# RandomNumberGenerator.net
KiCad netlist of a schematic drawn in Altium Designer
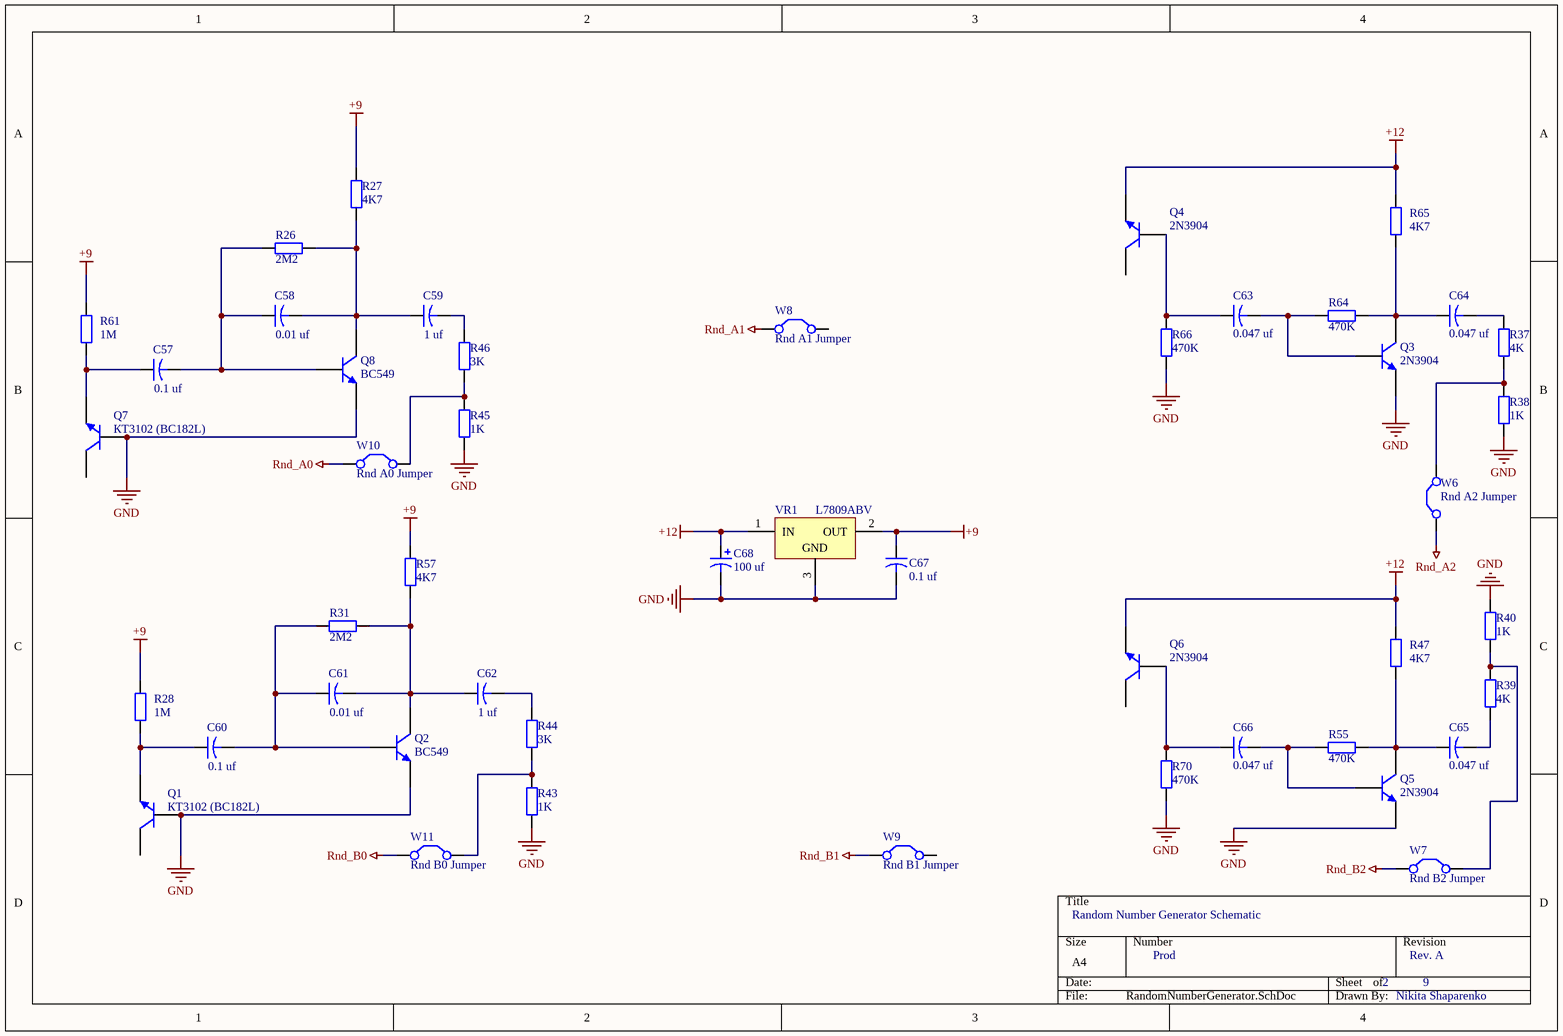
[diagram p0: RandomNumberGenerator.SchDoc]

(export (version "E")
  (design (tool "Eeschema 10.0.6"))
  (components
    (comp (ref "C57")
      (value "0.1 uf")
      (footprint "CAPR5-4X5")
      (description "Capacitor")
      (fields (field (name "Comment") "Cap2") (field (name "PUBLISHER") "Altium Limited"))
      (libsource (lib "Miscellaneous Devices") (part "Cap2"))
    )
    (comp (ref "C58")
      (value "0.01 uf")
      (footprint "CAPR5-4X5")
      (description "Capacitor")
      (fields (field (name "Comment") "Cap2") (field (name "PUBLISHER") "Altium Limited"))
      (libsource (lib "Miscellaneous Devices") (part "Cap2"))
    )
    (comp (ref "C59")
      (value "1 uf")
      (footprint "CAPR5-4X5")
      (description "Capacitor")
      (fields (field (name "Comment") "Cap2") (field (name "PUBLISHER") "Altium Limited"))
      (libsource (lib "Miscellaneous Devices") (part "Cap2"))
    )
    (comp (ref "C60")
      (value "0.1 uf")
      (footprint "CAPR5-4X5")
      (description "Capacitor")
      (fields (field (name "Comment") "Cap2") (field (name "PUBLISHER") "Altium Limited"))
      (libsource (lib "Miscellaneous Devices") (part "Cap2"))
    )
    (comp (ref "C61")
      (value "0.01 uf")
      (footprint "CAPR5-4X5")
      (description "Capacitor")
      (fields (field (name "Comment") "Cap2") (field (name "PUBLISHER") "Altium Limited"))
      (libsource (lib "Miscellaneous Devices") (part "Cap2"))
    )
    (comp (ref "C62")
      (value "1 uf")
      (footprint "CAPR5-4X5")
      (description "Capacitor")
      (fields (field (name "Comment") "Cap2") (field (name "PUBLISHER") "Altium Limited"))
      (libsource (lib "Miscellaneous Devices") (part "Cap2"))
    )
    (comp (ref "C63")
      (value "0.047 uf")
      (footprint "CAPR5-4X5")
      (description "Capacitor")
      (fields (field (name "Comment") "Cap2") (field (name "PUBLISHER") "Altium Limited"))
      (libsource (lib "Miscellaneous Devices") (part "Cap2"))
    )
    (comp (ref "C64")
      (value "0.047 uf")
      (footprint "CAPR5-4X5")
      (description "Capacitor")
      (fields (field (name "Comment") "Cap2") (field (name "PUBLISHER") "Altium Limited"))
      (libsource (lib "Miscellaneous Devices") (part "Cap2"))
    )
    (comp (ref "C65")
      (value "0.047 uf")
      (footprint "CAPR5-4X5")
      (description "Capacitor")
      (fields (field (name "Comment") "Cap2") (field (name "PUBLISHER") "Altium Limited"))
      (libsource (lib "Miscellaneous Devices") (part "Cap2"))
    )
    (comp (ref "C66")
      (value "0.047 uf")
      (footprint "CAPR5-4X5")
      (description "Capacitor")
      (fields (field (name "Comment") "Cap2") (field (name "PUBLISHER") "Altium Limited"))
      (libsource (lib "Miscellaneous Devices") (part "Cap2"))
    )
    (comp (ref "C67")
      (value "0.1 uf")
      (footprint "CAPR5-4X5")
      (description "Capacitor")
      (fields (field (name "Comment") "Cap2") (field (name "PUBLISHER") "Altium Limited"))
      (libsource (lib "Miscellaneous Devices") (part "Cap2"))
    )
    (comp (ref "C68")
      (value "100 uf")
      (footprint "RAD-0.2")
      (description "Polarized Capacitor (Radial)")
      (fields (field (name "Comment") "Cap Pol1") (field (name "PUBLISHER") "Altium Limited"))
      (libsource (lib "Miscellaneous Devices") (part "Cap Pol1"))
    )
    (comp (ref "Q1")
      (value "КТ3102 (BC182L)")
      (footprint "TO-226-AA")
      (description "NPN Bipolar Transistor")
      (fields (field (name "PUBLISHER") "Altium Limited"))
      (libsource (lib "Miscellaneous Devices") (part "NPN"))
    )
    (comp (ref "Q2")
      (value "BC549")
      (footprint "TO-226-AA")
      (description "NPN Bipolar Transistor")
      (fields (field (name "PUBLISHER") "Altium Limited"))
      (libsource (lib "Miscellaneous Devices") (part "NPN"))
    )
    (comp (ref "Q3")
      (value "2N3904")
      (footprint "TO-226-AA")
      (description "NPN Bipolar Transistor")
      (fields (field (name "PUBLISHER") "Altium Limited"))
      (libsource (lib "Miscellaneous Devices") (part "NPN"))
    )
    (comp (ref "Q4")
      (value "2N3904")
      (footprint "TO-226-AA")
      (description "NPN Bipolar Transistor")
      (fields (field (name "PUBLISHER") "Altium Limited"))
      (libsource (lib "Miscellaneous Devices") (part "NPN"))
    )
    (comp (ref "Q5")
      (value "2N3904")
      (footprint "TO-226-AA")
      (description "NPN Bipolar Transistor")
      (fields (field (name "PUBLISHER") "Altium Limited"))
      (libsource (lib "Miscellaneous Devices") (part "NPN"))
    )
    (comp (ref "Q6")
      (value "2N3904")
      (footprint "TO-226-AA")
      (description "NPN Bipolar Transistor")
      (fields (field (name "PUBLISHER") "Altium Limited"))
      (libsource (lib "Miscellaneous Devices") (part "NPN"))
    )
    (comp (ref "Q7")
      (value "КТ3102 (BC182L)")
      (footprint "TO-226-AA")
      (description "NPN Bipolar Transistor")
      (fields (field (name "PUBLISHER") "Altium Limited"))
      (libsource (lib "Miscellaneous Devices") (part "NPN"))
    )
    (comp (ref "Q8")
      (value "BC549")
      (footprint "TO-226-AA")
      (description "NPN Bipolar Transistor")
      (fields (field (name "PUBLISHER") "Altium Limited"))
      (libsource (lib "Miscellaneous Devices") (part "NPN"))
    )
    (comp (ref "R26")
      (value "2M2")
      (footprint "AXIAL-0.4")
      (description "Resistor")
      (fields (field (name "Comment") "Res2") (field (name "PUBLISHER") "Altium Limited"))
      (libsource (lib "") (part "Res2_1"))
    )
    (comp (ref "R27")
      (value "4K7")
      (footprint "AXIAL-0.4")
      (description "Resistor")
      (fields (field (name "Comment") "Res2") (field (name "PUBLISHER") "Altium Limited"))
      (libsource (lib "Miscellaneous Devices") (part "Res2"))
    )
    (comp (ref "R28")
      (value "1M")
      (footprint "AXIAL-0.4")
      (description "Resistor")
      (fields (field (name "Comment") "Res2") (field (name "PUBLISHER") "Altium Limited"))
      (libsource (lib "Miscellaneous Devices") (part "Res2"))
    )
    (comp (ref "R31")
      (value "2M2")
      (footprint "AXIAL-0.4")
      (description "Resistor")
      (fields (field (name "Comment") "Res2") (field (name "PUBLISHER") "Altium Limited"))
      (libsource (lib "") (part "Res2_1"))
    )
    (comp (ref "R37")
      (value "4K")
      (footprint "AXIAL-0.4")
      (description "Resistor")
      (fields (field (name "Comment") "Res2") (field (name "PUBLISHER") "Altium Limited"))
      (libsource (lib "Miscellaneous Devices") (part "Res2"))
    )
    (comp (ref "R38")
      (value "1K")
      (footprint "AXIAL-0.4")
      (description "Resistor")
      (fields (field (name "Comment") "Res2") (field (name "PUBLISHER") "Altium Limited"))
      (libsource (lib "Miscellaneous Devices") (part "Res2"))
    )
    (comp (ref "R39")
      (value "4K")
      (footprint "AXIAL-0.4")
      (description "Resistor")
      (fields (field (name "Comment") "Res2") (field (name "PUBLISHER") "Altium Limited"))
      (libsource (lib "") (part "Res2_2"))
    )
    (comp (ref "R40")
      (value "1K")
      (footprint "AXIAL-0.4")
      (description "Resistor")
      (fields (field (name "Comment") "Res2") (field (name "PUBLISHER") "Altium Limited"))
      (libsource (lib "") (part "Res2_2"))
    )
    (comp (ref "R43")
      (value "1K")
      (footprint "AXIAL-0.4")
      (description "Resistor")
      (fields (field (name "Comment") "Res2") (field (name "PUBLISHER") "Altium Limited"))
      (libsource (lib "Miscellaneous Devices") (part "Res2"))
    )
    (comp (ref "R44")
      (value "3K")
      (footprint "AXIAL-0.4")
      (description "Resistor")
      (fields (field (name "Comment") "Res2") (field (name "PUBLISHER") "Altium Limited"))
      (libsource (lib "Miscellaneous Devices") (part "Res2"))
    )
    (comp (ref "R45")
      (value "1K")
      (footprint "AXIAL-0.4")
      (description "Resistor")
      (fields (field (name "Comment") "Res2") (field (name "PUBLISHER") "Altium Limited"))
      (libsource (lib "Miscellaneous Devices") (part "Res2"))
    )
    (comp (ref "R46")
      (value "3K")
      (footprint "AXIAL-0.4")
      (description "Resistor")
      (fields (field (name "Comment") "Res2") (field (name "PUBLISHER") "Altium Limited"))
      (libsource (lib "Miscellaneous Devices") (part "Res2"))
    )
    (comp (ref "R47")
      (value "4K7")
      (footprint "AXIAL-0.4")
      (description "Resistor")
      (fields (field (name "Comment") "Res2") (field (name "PUBLISHER") "Altium Limited"))
      (libsource (lib "Miscellaneous Devices") (part "Res2"))
    )
    (comp (ref "R55")
      (value "470K")
      (footprint "AXIAL-0.4")
      (description "Resistor")
      (fields (field (name "Comment") "Res2") (field (name "PUBLISHER") "Altium Limited"))
      (libsource (lib "") (part "Res2_1"))
    )
    (comp (ref "R57")
      (value "4K7")
      (footprint "AXIAL-0.4")
      (description "Resistor")
      (fields (field (name "Comment") "Res2") (field (name "PUBLISHER") "Altium Limited"))
      (libsource (lib "Miscellaneous Devices") (part "Res2"))
    )
    (comp (ref "R61")
      (value "1M")
      (footprint "AXIAL-0.4")
      (description "Resistor")
      (fields (field (name "Comment") "Res2") (field (name "PUBLISHER") "Altium Limited"))
      (libsource (lib "Miscellaneous Devices") (part "Res2"))
    )
    (comp (ref "R64")
      (value "470K")
      (footprint "AXIAL-0.4")
      (description "Resistor")
      (fields (field (name "Comment") "Res2") (field (name "PUBLISHER") "Altium Limited"))
      (libsource (lib "") (part "Res2_1"))
    )
    (comp (ref "R65")
      (value "4K7")
      (footprint "AXIAL-0.4")
      (description "Resistor")
      (fields (field (name "Comment") "Res2") (field (name "PUBLISHER") "Altium Limited"))
      (libsource (lib "Miscellaneous Devices") (part "Res2"))
    )
    (comp (ref "R66")
      (value "470K")
      (footprint "AXIAL-0.4")
      (description "Resistor")
      (fields (field (name "Comment") "Res2") (field (name "PUBLISHER") "Altium Limited"))
      (libsource (lib "Miscellaneous Devices") (part "Res2"))
    )
    (comp (ref "R70")
      (value "470K")
      (footprint "AXIAL-0.4")
      (description "Resistor")
      (fields (field (name "Comment") "Res2") (field (name "PUBLISHER") "Altium Limited"))
      (libsource (lib "Miscellaneous Devices") (part "Res2"))
    )
    (comp (ref "VR1")
      (value "L7809ABV")
      (footprint "TO220ABN")
      (description "Precision 1A Regulator")
      (fields (field (name "PUBLISHER") "Altium Limited"))
      (libsource (lib "ST Power Mgt Voltage Regulator") (part "L7809ABV"))
    )
    (comp (ref "W6")
      (value "Rnd A2 Jumper")
      (footprint "RAD-0.2")
      (description "Jumper Wire")
      (fields (field (name "PUBLISHER") "Altium Limited"))
      (libsource (lib "Miscellaneous Devices") (part "Jumper"))
    )
    (comp (ref "W7")
      (value "Rnd B2 Jumper")
      (footprint "RAD-0.2")
      (description "Jumper Wire")
      (fields (field (name "PUBLISHER") "Altium Limited"))
      (libsource (lib "Miscellaneous Devices") (part "Jumper"))
    )
    (comp (ref "W8")
      (value "Rnd A1 Jumper")
      (footprint "RAD-0.2")
      (description "Jumper Wire")
      (fields (field (name "PUBLISHER") "Altium Limited"))
      (libsource (lib "Miscellaneous Devices") (part "Jumper"))
    )
    (comp (ref "W9")
      (value "Rnd B1 Jumper")
      (footprint "RAD-0.2")
      (description "Jumper Wire")
      (fields (field (name "PUBLISHER") "Altium Limited"))
      (libsource (lib "Miscellaneous Devices") (part "Jumper"))
    )
    (comp (ref "W10")
      (value "Rnd A0 Jumper")
      (footprint "RAD-0.2")
      (description "Jumper Wire")
      (fields (field (name "PUBLISHER") "Altium Limited"))
      (libsource (lib "Miscellaneous Devices") (part "Jumper"))
    )
    (comp (ref "W11")
      (value "Rnd B0 Jumper")
      (footprint "RAD-0.2")
      (description "Jumper Wire")
      (fields (field (name "PUBLISHER") "Altium Limited"))
      (libsource (lib "Miscellaneous Devices") (part "Jumper"))
    )
  )
  (nets
    (net (code "1") (name "+9") (class "Default")
      (node (ref "C67") (pin "1") (pinfunction "1_1") (pintype "passive"))
      (node (ref "R27") (pin "2") (pinfunction "2_2") (pintype "passive"))
      (node (ref "R28") (pin "2") (pinfunction "2_2") (pintype "passive"))
      (node (ref "R57") (pin "2") (pinfunction "2_2") (pintype "passive"))
      (node (ref "R61") (pin "2") (pinfunction "2_2") (pintype "passive"))
      (node (ref "VR1") (pin "2") (pinfunction "OUT_2") (pintype "power_in"))
    )
    (net (code "2") (name "+12") (class "Default")
      (node (ref "C68") (pin "1") (pinfunction "1_1") (pintype "passive"))
      (node (ref "Q4") (pin "3") (pinfunction "E_3") (pintype "passive"))
      (node (ref "Q6") (pin "3") (pinfunction "E_3") (pintype "passive"))
      (node (ref "R47") (pin "2") (pinfunction "2_2") (pintype "passive"))
      (node (ref "R65") (pin "2") (pinfunction "2_2") (pintype "passive"))
      (node (ref "VR1") (pin "1") (pinfunction "IN_1") (pintype "power_in"))
    )
    (net (code "3") (name "GND") (class "Default")
      (node (ref "C67") (pin "2") (pinfunction "2_2") (pintype "passive"))
      (node (ref "C68") (pin "2") (pinfunction "2_2") (pintype "passive"))
      (node (ref "Q1") (pin "2") (pinfunction "B_2") (pintype "passive"))
      (node (ref "Q2") (pin "3") (pinfunction "E_3") (pintype "passive"))
      (node (ref "Q3") (pin "3") (pinfunction "E_3") (pintype "passive"))
      (node (ref "Q5") (pin "3") (pinfunction "E_3") (pintype "passive"))
      (node (ref "Q7") (pin "2") (pinfunction "B_2") (pintype "passive"))
      (node (ref "Q8") (pin "3") (pinfunction "E_3") (pintype "passive"))
      (node (ref "R38") (pin "1") (pinfunction "1_1") (pintype "passive"))
      (node (ref "R40") (pin "1") (pinfunction "1_1") (pintype "passive"))
      (node (ref "R43") (pin "1") (pinfunction "1_1") (pintype "passive"))
      (node (ref "R45") (pin "1") (pinfunction "1_1") (pintype "passive"))
      (node (ref "R66") (pin "1") (pinfunction "1_1") (pintype "passive"))
      (node (ref "R70") (pin "1") (pinfunction "1_1") (pintype "passive"))
      (node (ref "VR1") (pin "3") (pinfunction "GND_3") (pintype "power_in"))
    )
    (net (code "4") (name "Net-(C59-Pad2)") (class "Default")
      (node (ref "C59") (pin "2") (pinfunction "2_2") (pintype "passive"))
      (node (ref "R46") (pin "2") (pinfunction "2_2") (pintype "passive"))
    )
    (net (code "5") (name "Net-(C62-Pad2)") (class "Default")
      (node (ref "C62") (pin "2") (pinfunction "2_2") (pintype "passive"))
      (node (ref "R44") (pin "2") (pinfunction "2_2") (pintype "passive"))
    )
    (net (code "6") (name "Net-(C64-Pad2)") (class "Default")
      (node (ref "C64") (pin "2") (pinfunction "2_2") (pintype "passive"))
      (node (ref "R37") (pin "2") (pinfunction "2_2") (pintype "passive"))
    )
    (net (code "7") (name "Net-(C65-Pad2)") (class "Default")
      (node (ref "C65") (pin "2") (pinfunction "2_2") (pintype "passive"))
      (node (ref "R39") (pin "2") (pinfunction "2_2") (pintype "passive"))
    )
    (net (code "8") (name "Net-(Q1-E)") (class "Default")
      (node (ref "C60") (pin "1") (pinfunction "1_1") (pintype "passive"))
      (node (ref "Q1") (pin "3") (pinfunction "E_3") (pintype "passive"))
      (node (ref "R28") (pin "1") (pinfunction "1_1") (pintype "passive"))
    )
    (net (code "9") (name "Net-(Q2-B)") (class "Default")
      (node (ref "C60") (pin "2") (pinfunction "2_2") (pintype "passive"))
      (node (ref "C61") (pin "1") (pinfunction "1_1") (pintype "passive"))
      (node (ref "Q2") (pin "2") (pinfunction "B_2") (pintype "passive"))
      (node (ref "R31") (pin "2") (pinfunction "2_2") (pintype "passive"))
    )
    (net (code "10") (name "Net-(Q2-C)") (class "Default")
      (node (ref "C61") (pin "2") (pinfunction "2_2") (pintype "passive"))
      (node (ref "C62") (pin "1") (pinfunction "1_1") (pintype "passive"))
      (node (ref "Q2") (pin "1") (pinfunction "C_1") (pintype "passive"))
      (node (ref "R31") (pin "1") (pinfunction "1_1") (pintype "passive"))
      (node (ref "R57") (pin "1") (pinfunction "1_1") (pintype "passive"))
    )
    (net (code "11") (name "Net-(Q3-B)") (class "Default")
      (node (ref "C63") (pin "2") (pinfunction "2_2") (pintype "passive"))
      (node (ref "Q3") (pin "2") (pinfunction "B_2") (pintype "passive"))
      (node (ref "R64") (pin "2") (pinfunction "2_2") (pintype "passive"))
    )
    (net (code "12") (name "Net-(Q3-C)") (class "Default")
      (node (ref "C64") (pin "1") (pinfunction "1_1") (pintype "passive"))
      (node (ref "Q3") (pin "1") (pinfunction "C_1") (pintype "passive"))
      (node (ref "R64") (pin "1") (pinfunction "1_1") (pintype "passive"))
      (node (ref "R65") (pin "1") (pinfunction "1_1") (pintype "passive"))
    )
    (net (code "13") (name "Net-(Q4-B)") (class "Default")
      (node (ref "C63") (pin "1") (pinfunction "1_1") (pintype "passive"))
      (node (ref "Q4") (pin "2") (pinfunction "B_2") (pintype "passive"))
      (node (ref "R66") (pin "2") (pinfunction "2_2") (pintype "passive"))
    )
    (net (code "14") (name "Net-(Q5-B)") (class "Default")
      (node (ref "C66") (pin "2") (pinfunction "2_2") (pintype "passive"))
      (node (ref "Q5") (pin "2") (pinfunction "B_2") (pintype "passive"))
      (node (ref "R55") (pin "2") (pinfunction "2_2") (pintype "passive"))
    )
    (net (code "15") (name "Net-(Q5-C)") (class "Default")
      (node (ref "C65") (pin "1") (pinfunction "1_1") (pintype "passive"))
      (node (ref "Q5") (pin "1") (pinfunction "C_1") (pintype "passive"))
      (node (ref "R47") (pin "1") (pinfunction "1_1") (pintype "passive"))
      (node (ref "R55") (pin "1") (pinfunction "1_1") (pintype "passive"))
    )
    (net (code "16") (name "Net-(Q6-B)") (class "Default")
      (node (ref "C66") (pin "1") (pinfunction "1_1") (pintype "passive"))
      (node (ref "Q6") (pin "2") (pinfunction "B_2") (pintype "passive"))
      (node (ref "R70") (pin "2") (pinfunction "2_2") (pintype "passive"))
    )
    (net (code "17") (name "Net-(Q7-E)") (class "Default")
      (node (ref "C57") (pin "1") (pinfunction "1_1") (pintype "passive"))
      (node (ref "Q7") (pin "3") (pinfunction "E_3") (pintype "passive"))
      (node (ref "R61") (pin "1") (pinfunction "1_1") (pintype "passive"))
    )
    (net (code "18") (name "Net-(Q8-B)") (class "Default")
      (node (ref "C57") (pin "2") (pinfunction "2_2") (pintype "passive"))
      (node (ref "C58") (pin "1") (pinfunction "1_1") (pintype "passive"))
      (node (ref "Q8") (pin "2") (pinfunction "B_2") (pintype "passive"))
      (node (ref "R26") (pin "2") (pinfunction "2_2") (pintype "passive"))
    )
    (net (code "19") (name "Net-(Q8-C)") (class "Default")
      (node (ref "C58") (pin "2") (pinfunction "2_2") (pintype "passive"))
      (node (ref "C59") (pin "1") (pinfunction "1_1") (pintype "passive"))
      (node (ref "Q8") (pin "1") (pinfunction "C_1") (pintype "passive"))
      (node (ref "R26") (pin "1") (pinfunction "1_1") (pintype "passive"))
      (node (ref "R27") (pin "1") (pinfunction "1_1") (pintype "passive"))
    )
    (net (code "20") (name "Net-(W6-C2)") (class "Default")
      (node (ref "R37") (pin "1") (pinfunction "1_1") (pintype "passive"))
      (node (ref "R38") (pin "2") (pinfunction "2_2") (pintype "passive"))
      (node (ref "W6") (pin "2") (pinfunction "C2_2") (pintype "passive"))
    )
    (net (code "21") (name "Net-(W7-C2)") (class "Default")
      (node (ref "R39") (pin "1") (pinfunction "1_1") (pintype "passive"))
      (node (ref "R40") (pin "2") (pinfunction "2_2") (pintype "passive"))
      (node (ref "W7") (pin "2") (pinfunction "C2_2") (pintype "passive"))
    )
    (net (code "22") (name "Net-(W10-C2)") (class "Default")
      (node (ref "R45") (pin "2") (pinfunction "2_2") (pintype "passive"))
      (node (ref "R46") (pin "1") (pinfunction "1_1") (pintype "passive"))
      (node (ref "W10") (pin "2") (pinfunction "C2_2") (pintype "passive"))
    )
    (net (code "23") (name "Net-(W11-C2)") (class "Default")
      (node (ref "R43") (pin "2") (pinfunction "2_2") (pintype "passive"))
      (node (ref "R44") (pin "1") (pinfunction "1_1") (pintype "passive"))
      (node (ref "W11") (pin "2") (pinfunction "C2_2") (pintype "passive"))
    )
    (net (code "24") (name "Rnd_A0") (class "Default")
      (node (ref "W10") (pin "1") (pinfunction "C1_1") (pintype "passive"))
    )
    (net (code "25") (name "Rnd_A1") (class "Default")
      (node (ref "W8") (pin "1") (pinfunction "C1_1") (pintype "passive"))
    )
    (net (code "26") (name "Rnd_A2") (class "Default")
      (node (ref "W6") (pin "1") (pinfunction "C1_1") (pintype "passive"))
    )
    (net (code "27") (name "Rnd_B0") (class "Default")
      (node (ref "W11") (pin "1") (pinfunction "C1_1") (pintype "passive"))
    )
    (net (code "28") (name "Rnd_B1") (class "Default")
      (node (ref "W9") (pin "1") (pinfunction "C1_1") (pintype "passive"))
    )
    (net (code "29") (name "Rnd_B2") (class "Default")
      (node (ref "W7") (pin "1") (pinfunction "C1_1") (pintype "passive"))
    )
    (net (code "30") (name "unconnected-(Q1-C-Pad1)") (class "Default")
      (node (ref "Q1") (pin "1") (pinfunction "C_1") (pintype "passive"))
    )
    (net (code "31") (name "unconnected-(Q4-C-Pad1)") (class "Default")
      (node (ref "Q4") (pin "1") (pinfunction "C_1") (pintype "passive"))
    )
    (net (code "32") (name "unconnected-(Q6-C-Pad1)") (class "Default")
      (node (ref "Q6") (pin "1") (pinfunction "C_1") (pintype "passive"))
    )
    (net (code "33") (name "unconnected-(Q7-C-Pad1)") (class "Default")
      (node (ref "Q7") (pin "1") (pinfunction "C_1") (pintype "passive"))
    )
    (net (code "34") (name "unconnected-(W8-C2-Pad2)") (class "Default")
      (node (ref "W8") (pin "2") (pinfunction "C2_2") (pintype "passive"))
    )
    (net (code "35") (name "unconnected-(W9-C2-Pad2)") (class "Default")
      (node (ref "W9") (pin "2") (pinfunction "C2_2") (pintype "passive"))
    )
  )
)
